# Reference_Schematic_2021-02-27.net
KiCad netlist of a schematic drawn in Altium Designer
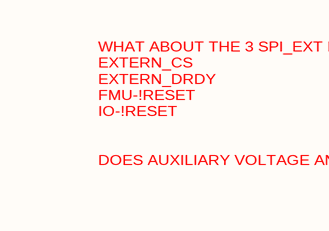
[diagram p0: Reference Schematic_2021-02-27.schdoc, top left]
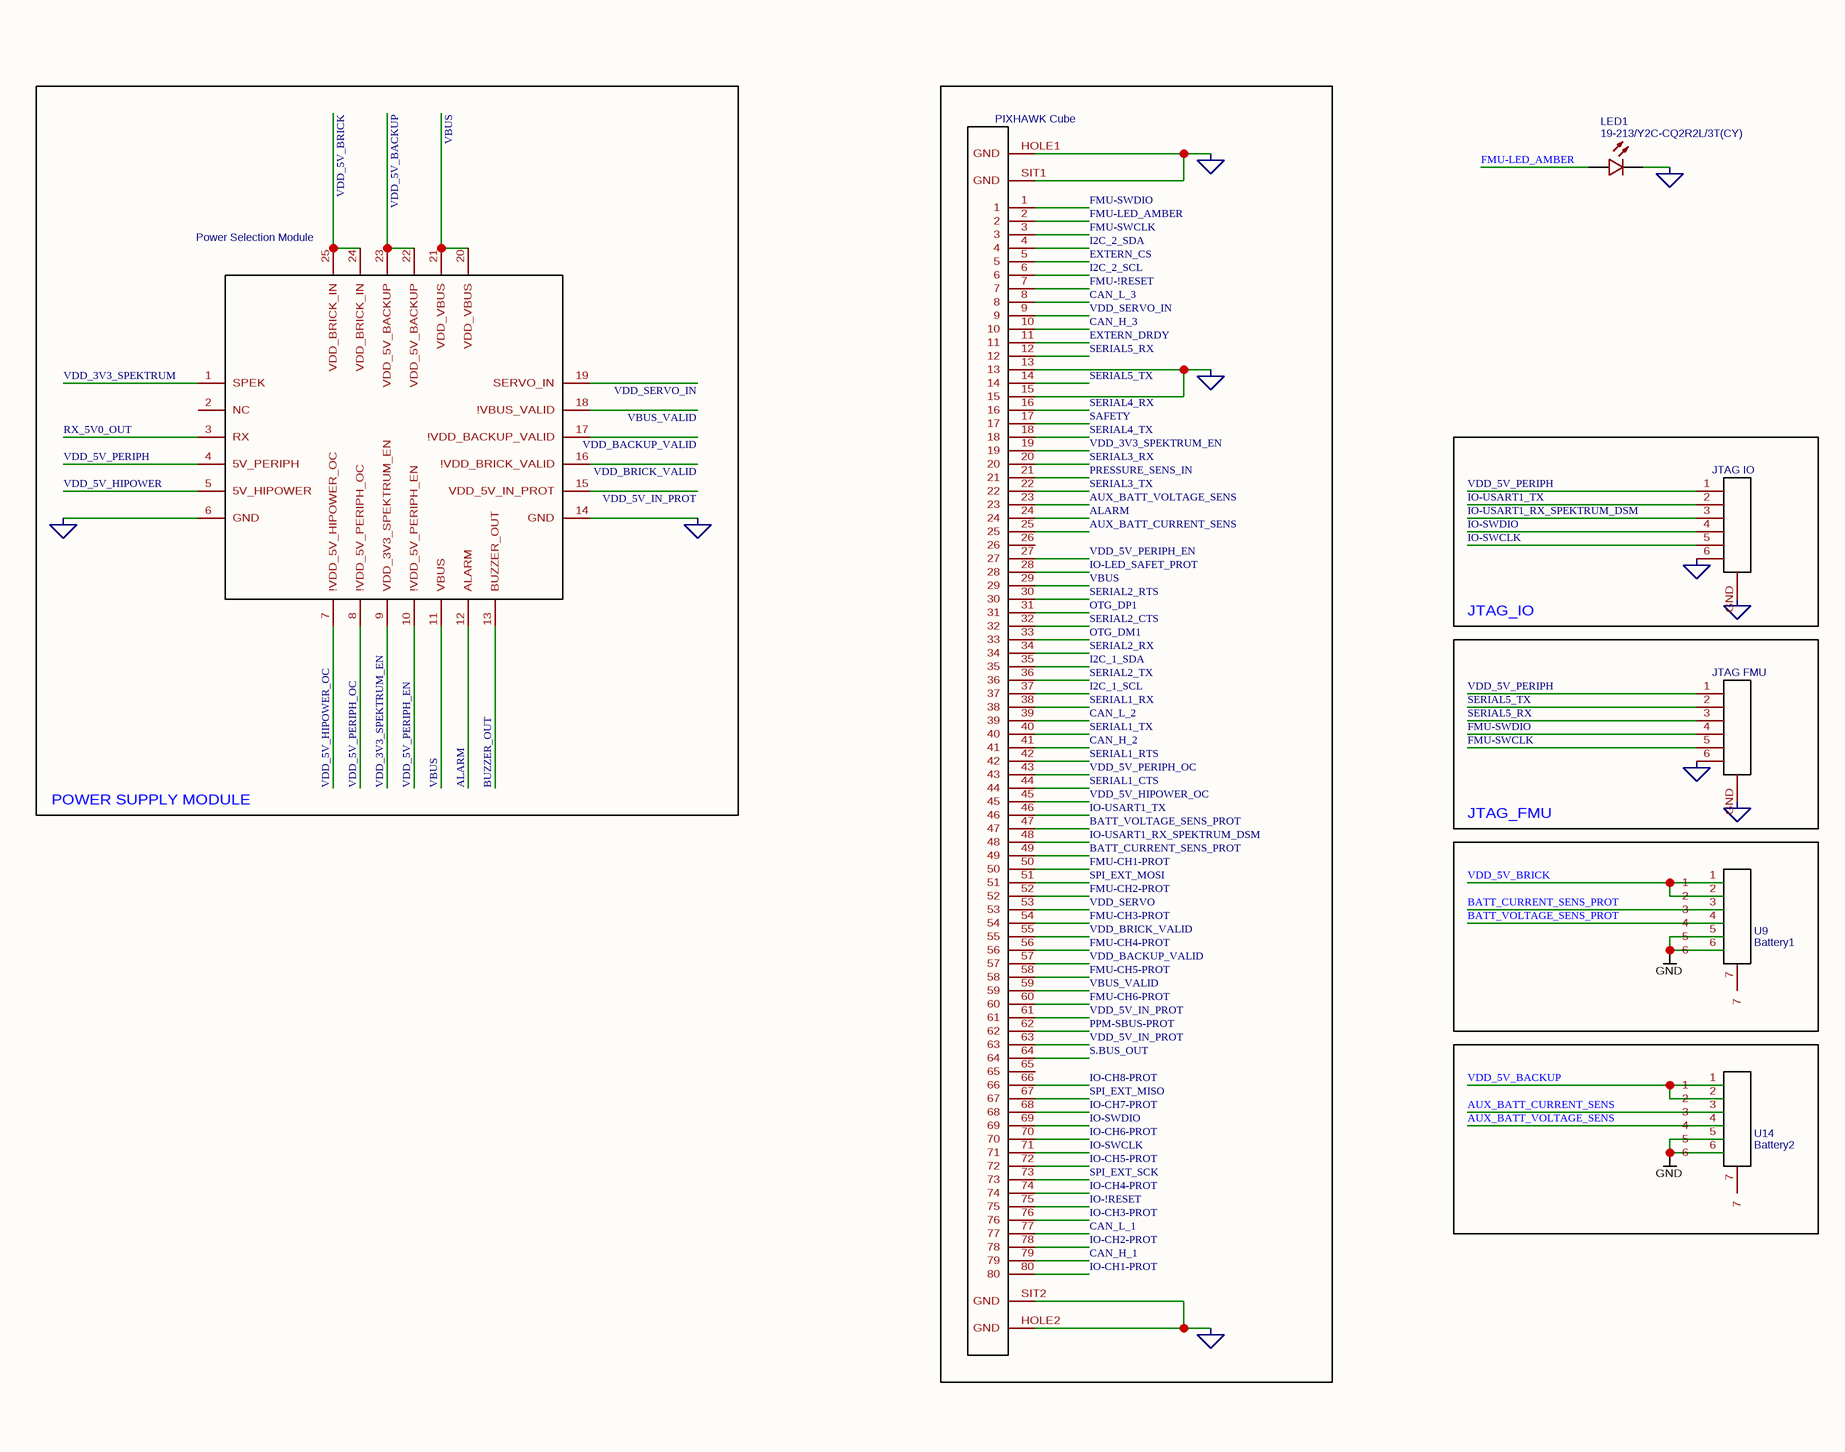
[diagram p1: Reference Schematic_2021-02-27.schdoc, bottom left]
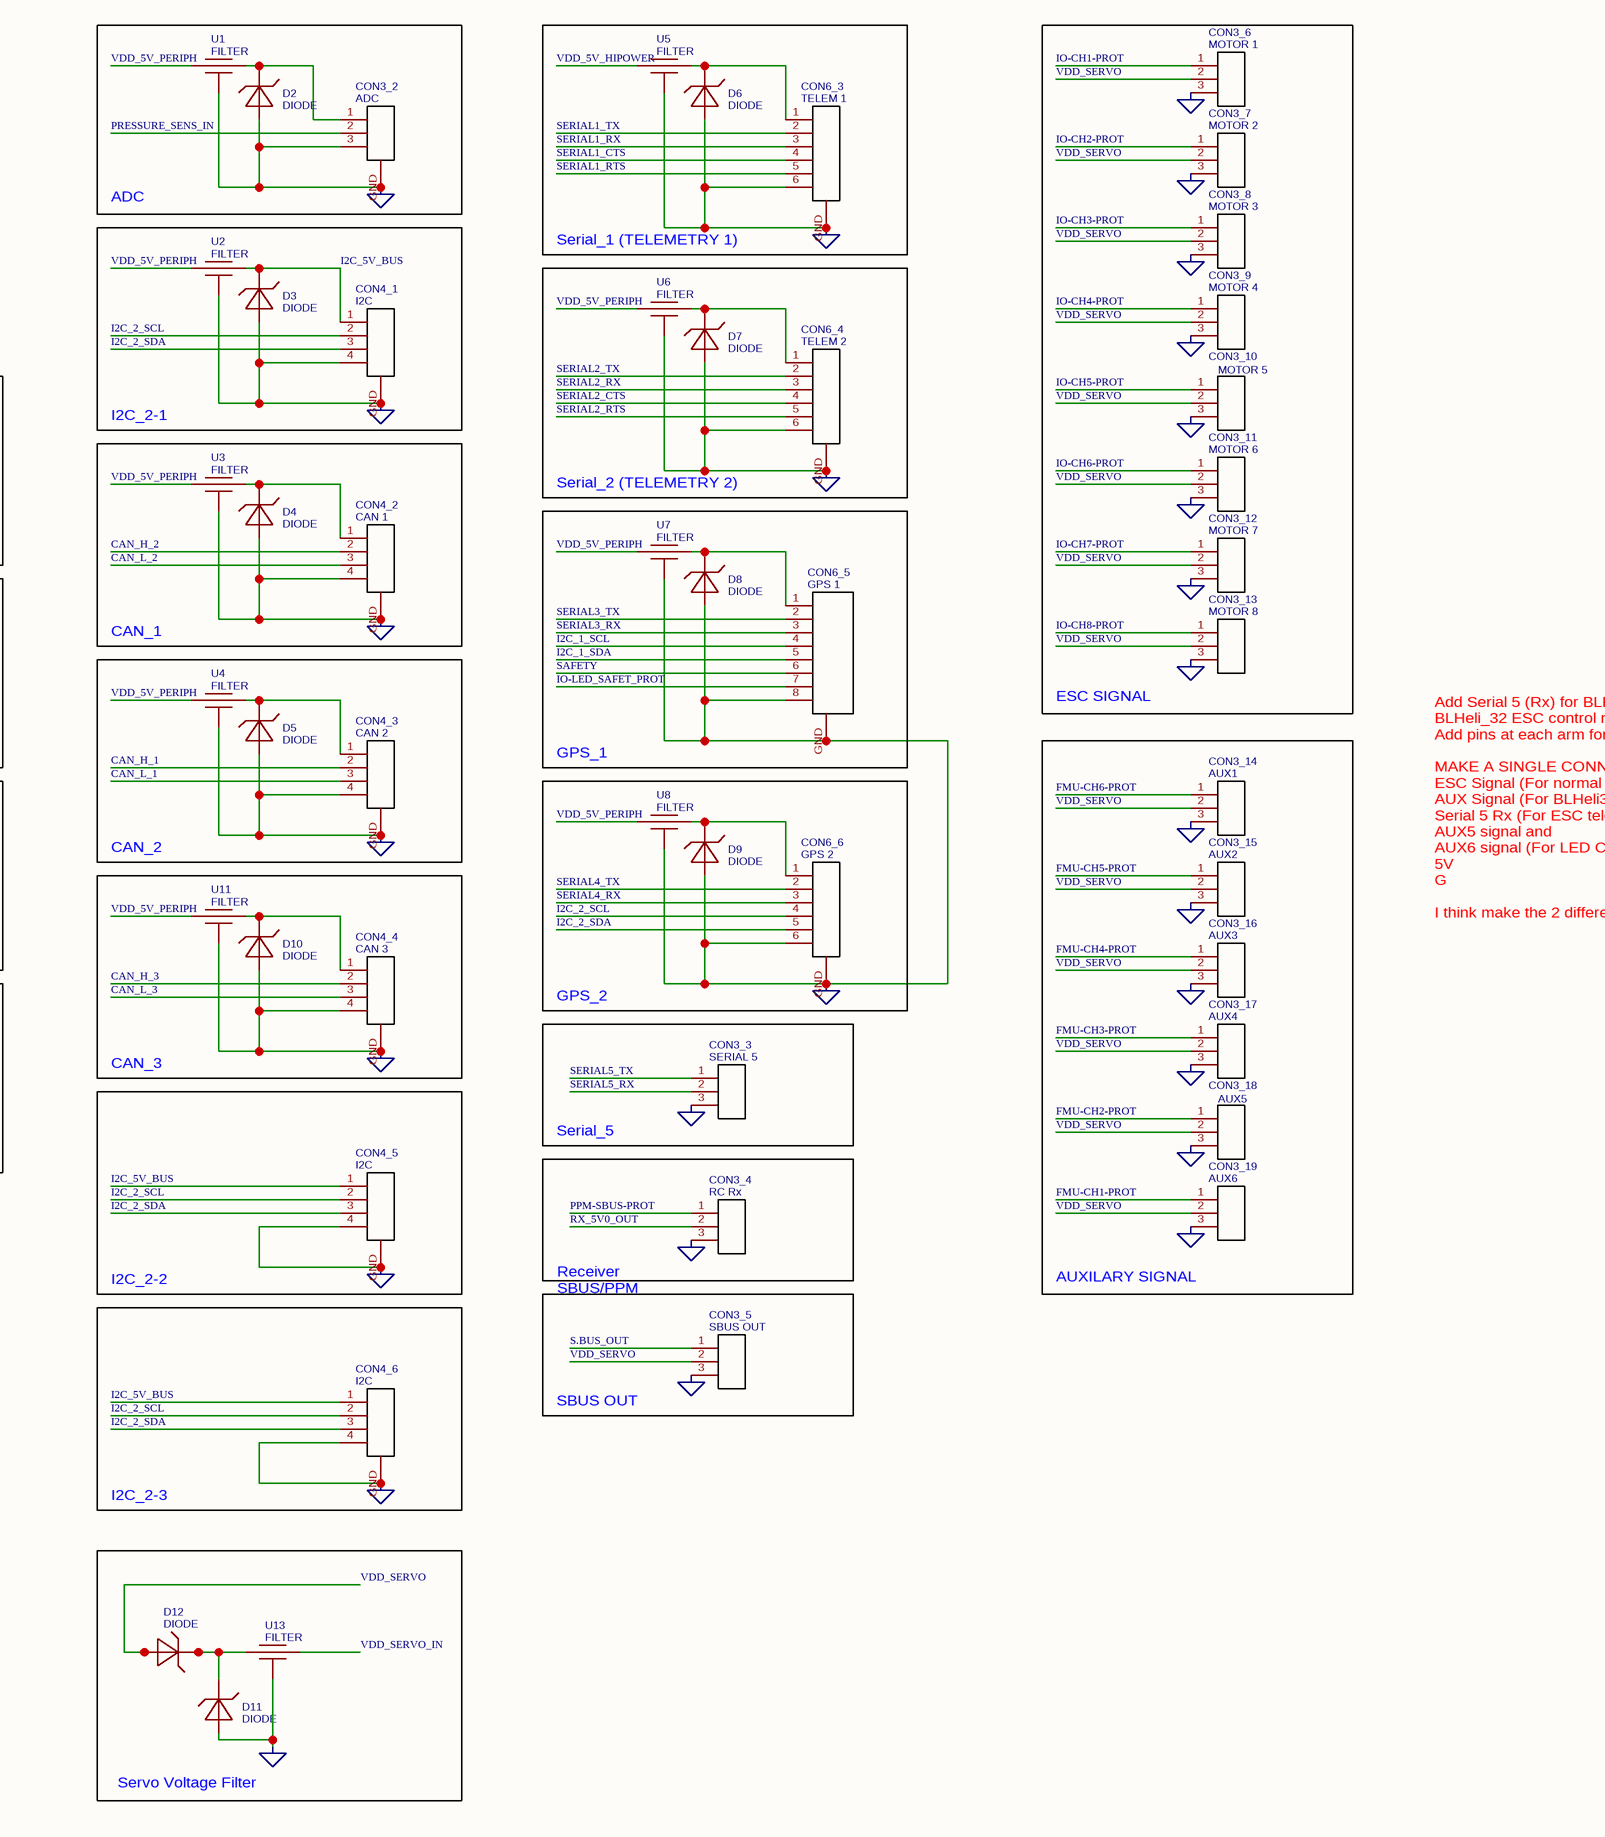
[diagram p2: Reference Schematic_2021-02-27.schdoc, bottom right]

(export (version "E")
  (design (tool "Eeschema 10.0.6"))
  (components
    (comp (ref "CON3_2")
      (value "ADC")
      (description "CONN HEADER GH TOP 3POS 1.25MM")
      (fields
        (field (name "BOM_MANUFACTURER PART") "BM03B-GHS-TBT(LF)(SN)(N)")
        (field (name "BOM_SUPPLIER PART") "455-1579-2-ND")
      )
      (libsource (lib "altium-import") (part "root_0_ADC_"))
    )
    (comp (ref "CON3_3")
      (value "SERIAL 5")
      (fields
        (field (name "BOM_MANUFACTURER PART") "894-70-012-10-001101")
        (field (name "BOM_SUPPLIER PART") "894-70-012-10-001101-ND")
      )
      (libsource (lib "altium-import") (part "root_0_SERIAL 5_"))
    )
    (comp (ref "CON3_4")
      (value "RC Rx")
      (fields
        (field (name "BOM_MANUFACTURER PART") "894-70-012-10-001101")
        (field (name "BOM_SUPPLIER PART") "894-70-012-10-001101-ND")
      )
      (libsource (lib "altium-import") (part "root_0_RC Rx_"))
    )
    (comp (ref "CON3_5")
      (value "SBUS OUT")
      (fields
        (field (name "BOM_MANUFACTURER PART") "894-70-012-10-001101")
        (field (name "BOM_SUPPLIER PART") "894-70-012-10-001101-ND")
      )
      (libsource (lib "altium-import") (part "root_0_SBUS OUT_"))
    )
    (comp (ref "CON3_6")
      (value "MOTOR 1")
      (fields
        (field (name "BOM_MANUFACTURER PART") "894-70-012-10-001101")
        (field (name "BOM_SUPPLIER PART") "894-70-012-10-001101-ND")
      )
      (libsource (lib "altium-import") (part "root_0_MOTOR 1_"))
    )
    (comp (ref "CON3_7")
      (value "MOTOR 2")
      (fields
        (field (name "BOM_MANUFACTURER PART") "894-70-012-10-001101")
        (field (name "BOM_SUPPLIER PART") "894-70-012-10-001101-ND")
      )
      (libsource (lib "altium-import") (part "root_0_MOTOR 2_"))
    )
    (comp (ref "CON3_8")
      (value "MOTOR 3")
      (fields
        (field (name "BOM_MANUFACTURER PART") "894-70-012-10-001101")
        (field (name "BOM_SUPPLIER PART") "894-70-012-10-001101-ND")
      )
      (libsource (lib "altium-import") (part "root_0_MOTOR 3_"))
    )
    (comp (ref "CON3_9")
      (value "MOTOR 4")
      (fields
        (field (name "BOM_MANUFACTURER PART") "894-70-012-10-001101")
        (field (name "BOM_SUPPLIER PART") "894-70-012-10-001101-ND")
      )
      (libsource (lib "altium-import") (part "root_0_MOTOR 4_"))
    )
    (comp (ref "CON3_10")
      (value "MOTOR 5")
      (fields
        (field (name "BOM_MANUFACTURER PART") "894-70-012-10-001101")
        (field (name "BOM_SUPPLIER PART") "894-70-012-10-001101-ND")
      )
      (libsource (lib "altium-import") (part "root_0_MOTOR 5_"))
    )
    (comp (ref "CON3_11")
      (value "MOTOR 6")
      (fields
        (field (name "BOM_MANUFACTURER PART") "894-70-012-10-001101")
        (field (name "BOM_SUPPLIER PART") "894-70-012-10-001101-ND")
      )
      (libsource (lib "altium-import") (part "root_0_MOTOR 6_"))
    )
    (comp (ref "CON3_12")
      (value "MOTOR 7")
      (fields
        (field (name "BOM_MANUFACTURER PART") "894-70-012-10-001101")
        (field (name "BOM_SUPPLIER PART") "894-70-012-10-001101-ND")
      )
      (libsource (lib "altium-import") (part "root_0_MOTOR 7_"))
    )
    (comp (ref "CON3_13")
      (value "MOTOR 8")
      (fields
        (field (name "BOM_MANUFACTURER PART") "894-70-012-10-001101")
        (field (name "BOM_SUPPLIER PART") "894-70-012-10-001101-ND")
      )
      (libsource (lib "altium-import") (part "root_0_MOTOR 8_"))
    )
    (comp (ref "CON3_14")
      (value "AUX1")
      (fields
        (field (name "BOM_MANUFACTURER PART") "894-70-012-10-001101")
        (field (name "BOM_SUPPLIER PART") "894-70-012-10-001101-ND")
      )
      (libsource (lib "altium-import") (part "root_0_AUX1_"))
    )
    (comp (ref "CON3_15")
      (value "AUX2")
      (fields
        (field (name "BOM_MANUFACTURER PART") "894-70-012-10-001101")
        (field (name "BOM_SUPPLIER PART") "894-70-012-10-001101-ND")
      )
      (libsource (lib "altium-import") (part "root_0_AUX2_"))
    )
    (comp (ref "CON3_16")
      (value "AUX3")
      (fields
        (field (name "BOM_MANUFACTURER PART") "894-70-012-10-001101")
        (field (name "BOM_SUPPLIER PART") "894-70-012-10-001101-ND")
      )
      (libsource (lib "altium-import") (part "root_0_AUX3_"))
    )
    (comp (ref "CON3_17")
      (value "AUX4")
      (fields
        (field (name "BOM_MANUFACTURER PART") "894-70-012-10-001101")
        (field (name "BOM_SUPPLIER PART") "894-70-012-10-001101-ND")
      )
      (libsource (lib "altium-import") (part "root_0_AUX4_"))
    )
    (comp (ref "CON3_18")
      (value "AUX5")
      (fields
        (field (name "BOM_MANUFACTURER PART") "894-70-012-10-001101")
        (field (name "BOM_SUPPLIER PART") "894-70-012-10-001101-ND")
      )
      (libsource (lib "altium-import") (part "root_0_AUX5_"))
    )
    (comp (ref "CON3_19")
      (value "AUX6")
      (fields
        (field (name "BOM_MANUFACTURER PART") "894-70-012-10-001101")
        (field (name "BOM_SUPPLIER PART") "894-70-012-10-001101-ND")
      )
      (libsource (lib "altium-import") (part "root_0_AUX6_"))
    )
    (comp (ref "CON4_1")
      (value "I2C")
      (description "CONN HEADER GH TOP 4POS 1.25MM")
      (fields
        (field (name "BOM_MANUFACTURER PART") "BM04B-GHS-TBT(LF)(SN)(N)")
        (field (name "BOM_SUPPLIER PART") "455-1580-2-ND")
      )
      (libsource (lib "altium-import") (part "root_0_I2C_"))
    )
    (comp (ref "CON4_2")
      (value "CAN 1")
      (description "CONN HEADER GH TOP 4POS 1.25MM")
      (fields
        (field (name "BOM_MANUFACTURER PART") "BM04B-GHS-TBT(LF)(SN)(N)")
        (field (name "BOM_SUPPLIER PART") "455-1580-2-ND")
      )
      (libsource (lib "altium-import") (part "root_0_CAN 1_"))
    )
    (comp (ref "CON4_3")
      (value "CAN 2")
      (description "CONN HEADER GH TOP 4POS 1.25MM")
      (fields
        (field (name "BOM_MANUFACTURER PART") "BM04B-GHS-TBT(LF)(SN)(N)")
        (field (name "BOM_SUPPLIER PART") "455-1580-2-ND")
      )
      (libsource (lib "altium-import") (part "root_0_CAN 2_"))
    )
    (comp (ref "CON4_4")
      (value "CAN 3")
      (description "CONN HEADER GH TOP 4POS 1.25MM")
      (fields
        (field (name "BOM_MANUFACTURER PART") "BM04B-GHS-TBT(LF)(SN)(N)")
        (field (name "BOM_SUPPLIER PART") "455-1580-2-ND")
      )
      (libsource (lib "altium-import") (part "root_0_CAN 3_"))
    )
    (comp (ref "CON4_5")
      (value "I2C")
      (description "CONN HEADER GH TOP 4POS 1.25MM")
      (fields
        (field (name "BOM_MANUFACTURER PART") "BM04B-GHS-TBT(LF)(SN)(N)")
        (field (name "BOM_SUPPLIER PART") "455-1580-2-ND")
      )
      (libsource (lib "altium-import") (part "root_0_I2C_"))
    )
    (comp (ref "CON4_6")
      (value "I2C")
      (description "CONN HEADER GH TOP 4POS 1.25MM")
      (fields
        (field (name "BOM_MANUFACTURER PART") "BM04B-GHS-TBT(LF)(SN)(N)")
        (field (name "BOM_SUPPLIER PART") "455-1580-2-ND")
      )
      (libsource (lib "altium-import") (part "root_0_I2C_"))
    )
    (comp (ref "CON6_1")
      (value "JTAG IO")
      (description "CONN HEADER SUR 6POS .8MM IDC")
      (fields
        (field (name "BOM_MANUFACTURER PART") "SM06B-SURS-TF(LF)(SN)")
        (field (name "BOM_SUPPLIER PART") "SM06B-SURS-TF(LF)(SN)-ND")
      )
      (libsource (lib "altium-import") (part "root_0_JTAG IO_"))
    )
    (comp (ref "CON6_2")
      (value "JTAG FMU")
      (description "CONN HEADER SUR 6POS .8MM IDC")
      (fields
        (field (name "BOM_MANUFACTURER PART") "SM06B-SURS-TF(LF)(SN)")
        (field (name "BOM_SUPPLIER PART") "SM06B-SURS-TF(LF)(SN)-ND")
      )
      (libsource (lib "altium-import") (part "root_0_JTAG FMU_"))
    )
    (comp (ref "CON6_3")
      (value "TELEM 1")
      (description "CONN HEADER GH TOP 6POS 1.25MM")
      (fields
        (field (name "BOM_MANUFACTURER PART") "BM06B-GHS-TBT(LF)(SN)(N)")
        (field (name "BOM_SUPPLIER PART") "455-1582-2-ND")
      )
      (libsource (lib "altium-import") (part "root_0_TELEM 1_"))
    )
    (comp (ref "CON6_4")
      (value "TELEM 2")
      (description "CONN HEADER GH TOP 6POS 1.25MM")
      (fields
        (field (name "BOM_MANUFACTURER PART") "BM06B-GHS-TBT(LF)(SN)(N)")
        (field (name "BOM_SUPPLIER PART") "455-1582-2-ND")
      )
      (libsource (lib "altium-import") (part "root_0_TELEM 2_"))
    )
    (comp (ref "CON6_5")
      (value "GPS 1")
      (description "CONN HEADER GH TOP 8POS 1.25MM")
      (fields
        (field (name "BOM_MANUFACTURER PART") "BM08B-GHS-TBT(LF)(SN)(N)")
        (field (name "BOM_SUPPLIER PART") "455-1584-2-ND")
      )
      (libsource (lib "altium-import") (part "root_0_GPS 1_"))
    )
    (comp (ref "CON6_6")
      (value "GPS 2")
      (description "CONN HEADER GH TOP 6POS 1.25MM")
      (fields
        (field (name "BOM_MANUFACTURER PART") "BM06B-GHS-TBT(LF)(SN)(N)")
        (field (name "BOM_SUPPLIER PART") "455-1582-2-ND")
      )
      (libsource (lib "altium-import") (part "root_0_GPS 2_"))
    )
    (comp (ref "D2")
      (value "DIODE")
      (fields
        (field (name "BOM_MANUFACTURER PART") "PESD0402-140")
        (field (name "BOM_SUPPLIER PART") "650-PESD0402-140")
      )
      (libsource (lib "altium-import") (part "root_3_DIODE_"))
    )
    (comp (ref "D3")
      (value "DIODE")
      (fields
        (field (name "BOM_MANUFACTURER PART") "PESD0402-140")
        (field (name "BOM_SUPPLIER PART") "650-PESD0402-140")
      )
      (libsource (lib "altium-import") (part "root_3_DIODE_"))
    )
    (comp (ref "D4")
      (value "DIODE")
      (fields
        (field (name "BOM_MANUFACTURER PART") "PESD0402-140")
        (field (name "BOM_SUPPLIER PART") "650-PESD0402-140")
      )
      (libsource (lib "altium-import") (part "root_3_DIODE_"))
    )
    (comp (ref "D5")
      (value "DIODE")
      (fields
        (field (name "BOM_MANUFACTURER PART") "PESD0402-140")
        (field (name "BOM_SUPPLIER PART") "650-PESD0402-140")
      )
      (libsource (lib "altium-import") (part "root_3_DIODE_"))
    )
    (comp (ref "D6")
      (value "DIODE")
      (fields
        (field (name "BOM_MANUFACTURER PART") "PESD0402-140")
        (field (name "BOM_SUPPLIER PART") "650-PESD0402-140")
      )
      (libsource (lib "altium-import") (part "root_3_DIODE_"))
    )
    (comp (ref "D7")
      (value "DIODE")
      (fields
        (field (name "BOM_MANUFACTURER PART") "PESD0402-140")
        (field (name "BOM_SUPPLIER PART") "650-PESD0402-140")
      )
      (libsource (lib "altium-import") (part "root_3_DIODE_"))
    )
    (comp (ref "D8")
      (value "DIODE")
      (fields
        (field (name "BOM_MANUFACTURER PART") "PESD0402-140")
        (field (name "BOM_SUPPLIER PART") "650-PESD0402-140")
      )
      (libsource (lib "altium-import") (part "root_3_DIODE_"))
    )
    (comp (ref "D9")
      (value "DIODE")
      (fields
        (field (name "BOM_MANUFACTURER PART") "PESD0402-140")
        (field (name "BOM_SUPPLIER PART") "650-PESD0402-140")
      )
      (libsource (lib "altium-import") (part "root_3_DIODE_"))
    )
    (comp (ref "D10")
      (value "DIODE")
      (fields
        (field (name "BOM_MANUFACTURER PART") "PESD0402-140")
        (field (name "BOM_SUPPLIER PART") "650-PESD0402-140")
      )
      (libsource (lib "altium-import") (part "root_3_DIODE_"))
    )
    (comp (ref "D11")
      (value "DIODE")
      (fields
        (field (name "BOM_MANUFACTURER PART") "PESD0402-140")
        (field (name "BOM_SUPPLIER PART") "650-PESD0402-140")
      )
      (libsource (lib "altium-import") (part "root_3_DIODE_"))
    )
    (comp (ref "D12")
      (value "DIODE")
      (fields
        (field (name "BOM_MANUFACTURER PART") "MSS1P4-M3/89A")
        (field (name "BOM_SUPPLIER PART") "05W6894")
      )
      (libsource (lib "altium-import") (part "root_2_DIODE_"))
    )
    (comp (ref "DF17(1.0H)-80DP-0.5V(57)")
      (value "PIXHAWK Cube")
      (fields
        (field (name "BOM_MANUFACTURER PART") "DF17(1.0H)-80DP-0.5V(57)")
        (field (name "BOM_SUPPLIER PART") "798-DF1710H80DP05V57")
      )
      (libsource (lib "altium-import") (part "root_0_PIXHAWK Cube_"))
    )
    (comp (ref "LED1")
      (value "19-213/Y2C-CQ2R2L/3T(CY)")
      (fields (field (name "BOM_SUPPLIER PART") "C72038"))
      (libsource (lib "altium-import") (part "root_0_19-213/Y2C-CQ2R2L/3T(CY)_"))
    )
    (comp (ref "PSM")
      (value "Power Selection Module")
      (fields (field (name "BOM_SUPPLIER PART") "PSM_C"))
      (libsource (lib "altium-import") (part "root_0_Power Selection Module_"))
    )
    (comp (ref "U1")
      (value "FILTER")
      (fields
        (field (name "BOM_MANUFACTURER PART") "NFM18PC104R1C3D")
        (field (name "BOM_SUPPLIER PART") "490-6969-2-ND")
      )
      (libsource (lib "altium-import") (part "root_0_FILTER_"))
    )
    (comp (ref "U2")
      (value "FILTER")
      (fields
        (field (name "BOM_MANUFACTURER PART") "NFM18PC104R1C3D")
        (field (name "BOM_SUPPLIER PART") "490-6969-2-ND")
      )
      (libsource (lib "altium-import") (part "root_0_FILTER_"))
    )
    (comp (ref "U3")
      (value "FILTER")
      (fields
        (field (name "BOM_MANUFACTURER PART") "NFM18PC104R1C3D")
        (field (name "BOM_SUPPLIER PART") "490-6969-2-ND")
      )
      (libsource (lib "altium-import") (part "root_0_FILTER_"))
    )
    (comp (ref "U4")
      (value "FILTER")
      (fields
        (field (name "BOM_MANUFACTURER PART") "NFM18PC104R1C3D")
        (field (name "BOM_SUPPLIER PART") "490-6969-2-ND")
      )
      (libsource (lib "altium-import") (part "root_0_FILTER_"))
    )
    (comp (ref "U5")
      (value "FILTER")
      (fields
        (field (name "BOM_MANUFACTURER PART") "NFM18PC104R1C3D")
        (field (name "BOM_SUPPLIER PART") "490-6969-2-ND")
      )
      (libsource (lib "altium-import") (part "root_0_FILTER_"))
    )
    (comp (ref "U6")
      (value "FILTER")
      (fields
        (field (name "BOM_MANUFACTURER PART") "NFM18PC104R1C3D")
        (field (name "BOM_SUPPLIER PART") "490-6969-2-ND")
      )
      (libsource (lib "altium-import") (part "root_0_FILTER_"))
    )
    (comp (ref "U7")
      (value "FILTER")
      (fields
        (field (name "BOM_MANUFACTURER PART") "NFM18PC104R1C3D")
        (field (name "BOM_SUPPLIER PART") "490-6969-2-ND")
      )
      (libsource (lib "altium-import") (part "root_0_FILTER_"))
    )
    (comp (ref "U8")
      (value "FILTER")
      (fields
        (field (name "BOM_MANUFACTURER PART") "NFM18PC104R1C3D")
        (field (name "BOM_SUPPLIER PART") "490-6969-2-ND")
      )
      (libsource (lib "altium-import") (part "root_0_FILTER_"))
    )
    (comp (ref "U9")
      (value "Battery1")
      (fields (field (name "BOM_MANUFACTURER PART") "502443-0670"))
      (libsource (lib "altium-import") (part "root_0_Battery1_"))
    )
    (comp (ref "U11")
      (value "FILTER")
      (fields
        (field (name "BOM_MANUFACTURER PART") "NFM18PC104R1C3D")
        (field (name "BOM_SUPPLIER PART") "490-6969-2-ND")
      )
      (libsource (lib "altium-import") (part "root_0_FILTER_"))
    )
    (comp (ref "U13")
      (value "FILTER")
      (fields
        (field (name "BOM_MANUFACTURER PART") "NFM18PC104R1C3D")
        (field (name "BOM_SUPPLIER PART") "490-6969-2-ND")
      )
      (libsource (lib "altium-import") (part "root_0_FILTER_"))
    )
    (comp (ref "U14")
      (value "Battery2")
      (fields (field (name "BOM_MANUFACTURER PART") "502443-0670"))
      (libsource (lib "altium-import") (part "root_0_Battery2_"))
    )
  )
  (nets
    (net (code "1") (name "/ALARM") (class "Default")
      (node (ref "DF17(1.0H)-80DP-0.5V(57)") (pin "24") (pinfunction "24_24") (pintype "passive"))
      (node (ref "PSM") (pin "12") (pinfunction "ALARM_12") (pintype "passive"))
    )
    (net (code "2") (name "/AUX_BATT_CURRENT_SENS") (class "Default")
      (node (ref "DF17(1.0H)-80DP-0.5V(57)") (pin "25") (pinfunction "25_25") (pintype "passive"))
      (node (ref "U14") (pin "3") (pinfunction "3_3") (pintype "passive"))
    )
    (net (code "3") (name "/AUX_BATT_VOLTAGE_SENS") (class "Default")
      (node (ref "DF17(1.0H)-80DP-0.5V(57)") (pin "23") (pinfunction "23_23") (pintype "passive"))
      (node (ref "U14") (pin "4") (pinfunction "4_4") (pintype "passive"))
    )
    (net (code "4") (name "/BATT_CURRENT_SENS_PROT") (class "Default")
      (node (ref "DF17(1.0H)-80DP-0.5V(57)") (pin "49") (pinfunction "49_49") (pintype "passive"))
      (node (ref "U9") (pin "3") (pinfunction "3_3") (pintype "passive"))
    )
    (net (code "5") (name "/BATT_VOLTAGE_SENS_PROT") (class "Default")
      (node (ref "DF17(1.0H)-80DP-0.5V(57)") (pin "47") (pinfunction "47_47") (pintype "passive"))
      (node (ref "U9") (pin "4") (pinfunction "4_4") (pintype "passive"))
    )
    (net (code "6") (name "/BUZZER_OUT") (class "Default")
      (node (ref "PSM") (pin "13") (pinfunction "BUZZER_OUT_13") (pintype "passive"))
    )
    (net (code "7") (name "/CAN_H_1") (class "Default")
      (node (ref "CON4_3") (pin "2") (pinfunction "2_2") (pintype "passive"))
      (node (ref "DF17(1.0H)-80DP-0.5V(57)") (pin "79") (pinfunction "79_79") (pintype "passive"))
    )
    (net (code "8") (name "/CAN_H_2") (class "Default")
      (node (ref "CON4_2") (pin "2") (pinfunction "2_2") (pintype "passive"))
      (node (ref "DF17(1.0H)-80DP-0.5V(57)") (pin "41") (pinfunction "41_41") (pintype "passive"))
    )
    (net (code "9") (name "/CAN_H_3") (class "Default")
      (node (ref "CON4_4") (pin "2") (pinfunction "2_2") (pintype "passive"))
      (node (ref "DF17(1.0H)-80DP-0.5V(57)") (pin "10") (pinfunction "10_10") (pintype "passive"))
    )
    (net (code "10") (name "/CAN_L_1") (class "Default")
      (node (ref "CON4_3") (pin "3") (pinfunction "3_3") (pintype "passive"))
      (node (ref "DF17(1.0H)-80DP-0.5V(57)") (pin "77") (pinfunction "77_77") (pintype "passive"))
    )
    (net (code "11") (name "/CAN_L_2") (class "Default")
      (node (ref "CON4_2") (pin "3") (pinfunction "3_3") (pintype "passive"))
      (node (ref "DF17(1.0H)-80DP-0.5V(57)") (pin "39") (pinfunction "39_39") (pintype "passive"))
    )
    (net (code "12") (name "/CAN_L_3") (class "Default")
      (node (ref "CON4_4") (pin "3") (pinfunction "3_3") (pintype "passive"))
      (node (ref "DF17(1.0H)-80DP-0.5V(57)") (pin "8") (pinfunction "8_8") (pintype "passive"))
    )
    (net (code "13") (name "/EXTERN_CS") (class "Default")
      (node (ref "DF17(1.0H)-80DP-0.5V(57)") (pin "5") (pinfunction "5_5") (pintype "passive"))
    )
    (net (code "14") (name "/EXTERN_DRDY") (class "Default")
      (node (ref "DF17(1.0H)-80DP-0.5V(57)") (pin "11") (pinfunction "11_11") (pintype "passive"))
    )
    (net (code "15") (name "/FMU-!RESET") (class "Default")
      (node (ref "DF17(1.0H)-80DP-0.5V(57)") (pin "7") (pinfunction "7_7") (pintype "passive"))
    )
    (net (code "16") (name "/FMU-CH1-PROT") (class "Default")
      (node (ref "CON3_19") (pin "1") (pinfunction "1_1") (pintype "passive"))
      (node (ref "DF17(1.0H)-80DP-0.5V(57)") (pin "50") (pinfunction "50_50") (pintype "passive"))
    )
    (net (code "17") (name "/FMU-CH2-PROT") (class "Default")
      (node (ref "CON3_18") (pin "1") (pinfunction "1_1") (pintype "passive"))
      (node (ref "DF17(1.0H)-80DP-0.5V(57)") (pin "52") (pinfunction "52_52") (pintype "passive"))
    )
    (net (code "18") (name "/FMU-CH3-PROT") (class "Default")
      (node (ref "CON3_17") (pin "1") (pinfunction "1_1") (pintype "passive"))
      (node (ref "DF17(1.0H)-80DP-0.5V(57)") (pin "54") (pinfunction "54_54") (pintype "passive"))
    )
    (net (code "19") (name "/FMU-CH4-PROT") (class "Default")
      (node (ref "CON3_16") (pin "1") (pinfunction "1_1") (pintype "passive"))
      (node (ref "DF17(1.0H)-80DP-0.5V(57)") (pin "56") (pinfunction "56_56") (pintype "passive"))
    )
    (net (code "20") (name "/FMU-CH5-PROT") (class "Default")
      (node (ref "CON3_15") (pin "1") (pinfunction "1_1") (pintype "passive"))
      (node (ref "DF17(1.0H)-80DP-0.5V(57)") (pin "58") (pinfunction "58_58") (pintype "passive"))
    )
    (net (code "21") (name "/FMU-CH6-PROT") (class "Default")
      (node (ref "CON3_14") (pin "1") (pinfunction "1_1") (pintype "passive"))
      (node (ref "DF17(1.0H)-80DP-0.5V(57)") (pin "60") (pinfunction "60_60") (pintype "passive"))
    )
    (net (code "22") (name "/FMU-LED_AMBER") (class "Default")
      (node (ref "DF17(1.0H)-80DP-0.5V(57)") (pin "2") (pinfunction "2_2") (pintype "passive"))
      (node (ref "LED1") (pin "1") (pinfunction "A_1") (pintype "passive"))
    )
    (net (code "23") (name "/FMU-SWCLK") (class "Default")
      (node (ref "CON6_2") (pin "5") (pinfunction "5_5") (pintype "passive"))
      (node (ref "DF17(1.0H)-80DP-0.5V(57)") (pin "3") (pinfunction "3_3") (pintype "passive"))
    )
    (net (code "24") (name "/FMU-SWDIO") (class "Default")
      (node (ref "CON6_2") (pin "4") (pinfunction "4_4") (pintype "passive"))
      (node (ref "DF17(1.0H)-80DP-0.5V(57)") (pin "1") (pinfunction "1_1") (pintype "passive"))
    )
    (net (code "25") (name "/I2C_1_SCL") (class "Default")
      (node (ref "CON6_5") (pin "4") (pinfunction "4_4") (pintype "passive"))
      (node (ref "DF17(1.0H)-80DP-0.5V(57)") (pin "37") (pinfunction "37_37") (pintype "passive"))
    )
    (net (code "26") (name "/I2C_1_SDA") (class "Default")
      (node (ref "CON6_5") (pin "5") (pinfunction "5_5") (pintype "passive"))
      (node (ref "DF17(1.0H)-80DP-0.5V(57)") (pin "35") (pinfunction "35_35") (pintype "passive"))
    )
    (net (code "27") (name "/I2C_2_SCL") (class "Default")
      (node (ref "CON4_1") (pin "2") (pinfunction "2_2") (pintype "passive"))
      (node (ref "CON4_5") (pin "2") (pinfunction "2_2") (pintype "passive"))
      (node (ref "CON4_6") (pin "2") (pinfunction "2_2") (pintype "passive"))
      (node (ref "CON6_6") (pin "4") (pinfunction "4_4") (pintype "passive"))
      (node (ref "DF17(1.0H)-80DP-0.5V(57)") (pin "6") (pinfunction "6_6") (pintype "passive"))
    )
    (net (code "28") (name "/I2C_2_SDA") (class "Default")
      (node (ref "CON4_1") (pin "3") (pinfunction "3_3") (pintype "passive"))
      (node (ref "CON4_5") (pin "3") (pinfunction "3_3") (pintype "passive"))
      (node (ref "CON4_6") (pin "3") (pinfunction "3_3") (pintype "passive"))
      (node (ref "CON6_6") (pin "5") (pinfunction "5_5") (pintype "passive"))
      (node (ref "DF17(1.0H)-80DP-0.5V(57)") (pin "4") (pinfunction "4_4") (pintype "passive"))
    )
    (net (code "29") (name "/I2C_5V_BUS") (class "Default")
      (node (ref "CON4_1") (pin "1") (pinfunction "1_1") (pintype "passive"))
      (node (ref "CON4_5") (pin "1") (pinfunction "1_1") (pintype "passive"))
      (node (ref "CON4_6") (pin "1") (pinfunction "1_1") (pintype "passive"))
      (node (ref "D3") (pin "1") (pinfunction "1_1") (pintype "passive"))
      (node (ref "U2") (pin "2") (pinfunction "2_2") (pintype "passive"))
    )
    (net (code "30") (name "/IO-!RESET") (class "Default")
      (node (ref "DF17(1.0H)-80DP-0.5V(57)") (pin "75") (pinfunction "75_75") (pintype "passive"))
    )
    (net (code "31") (name "/IO-CH1-PROT") (class "Default")
      (node (ref "CON3_6") (pin "1") (pinfunction "1_1") (pintype "passive"))
      (node (ref "DF17(1.0H)-80DP-0.5V(57)") (pin "80") (pinfunction "80_80") (pintype "passive"))
    )
    (net (code "32") (name "/IO-CH2-PROT") (class "Default")
      (node (ref "CON3_7") (pin "1") (pinfunction "1_1") (pintype "passive"))
      (node (ref "DF17(1.0H)-80DP-0.5V(57)") (pin "78") (pinfunction "78_78") (pintype "passive"))
    )
    (net (code "33") (name "/IO-CH3-PROT") (class "Default")
      (node (ref "CON3_8") (pin "1") (pinfunction "1_1") (pintype "passive"))
      (node (ref "DF17(1.0H)-80DP-0.5V(57)") (pin "76") (pinfunction "76_76") (pintype "passive"))
    )
    (net (code "34") (name "/IO-CH4-PROT") (class "Default")
      (node (ref "CON3_9") (pin "1") (pinfunction "1_1") (pintype "passive"))
      (node (ref "DF17(1.0H)-80DP-0.5V(57)") (pin "74") (pinfunction "74_74") (pintype "passive"))
    )
    (net (code "35") (name "/IO-CH5-PROT") (class "Default")
      (node (ref "CON3_10") (pin "1") (pinfunction "1_1") (pintype "passive"))
      (node (ref "DF17(1.0H)-80DP-0.5V(57)") (pin "72") (pinfunction "72_72") (pintype "passive"))
    )
    (net (code "36") (name "/IO-CH6-PROT") (class "Default")
      (node (ref "CON3_11") (pin "1") (pinfunction "1_1") (pintype "passive"))
      (node (ref "DF17(1.0H)-80DP-0.5V(57)") (pin "70") (pinfunction "70_70") (pintype "passive"))
    )
    (net (code "37") (name "/IO-CH7-PROT") (class "Default")
      (node (ref "CON3_12") (pin "1") (pinfunction "1_1") (pintype "passive"))
      (node (ref "DF17(1.0H)-80DP-0.5V(57)") (pin "68") (pinfunction "68_68") (pintype "passive"))
    )
    (net (code "38") (name "/IO-CH8-PROT") (class "Default")
      (node (ref "CON3_13") (pin "1") (pinfunction "1_1") (pintype "passive"))
      (node (ref "DF17(1.0H)-80DP-0.5V(57)") (pin "66") (pinfunction "66_66") (pintype "passive"))
    )
    (net (code "39") (name "/IO-LED_SAFET_PROT") (class "Default")
      (node (ref "CON6_5") (pin "7") (pinfunction "7_7") (pintype "passive"))
      (node (ref "DF17(1.0H)-80DP-0.5V(57)") (pin "28") (pinfunction "28_28") (pintype "passive"))
    )
    (net (code "40") (name "/IO-SWCLK") (class "Default")
      (node (ref "CON6_1") (pin "5") (pinfunction "5_5") (pintype "passive"))
      (node (ref "DF17(1.0H)-80DP-0.5V(57)") (pin "71") (pinfunction "71_71") (pintype "passive"))
    )
    (net (code "41") (name "/IO-SWDIO") (class "Default")
      (node (ref "CON6_1") (pin "4") (pinfunction "4_4") (pintype "passive"))
      (node (ref "DF17(1.0H)-80DP-0.5V(57)") (pin "69") (pinfunction "69_69") (pintype "passive"))
    )
    (net (code "42") (name "/IO-USART1_RX_SPEKTRUM_DSM") (class "Default")
      (node (ref "CON6_1") (pin "3") (pinfunction "3_3") (pintype "passive"))
      (node (ref "DF17(1.0H)-80DP-0.5V(57)") (pin "48") (pinfunction "48_48") (pintype "passive"))
    )
    (net (code "43") (name "/IO-USART1_TX") (class "Default")
      (node (ref "CON6_1") (pin "2") (pinfunction "2_2") (pintype "passive"))
      (node (ref "DF17(1.0H)-80DP-0.5V(57)") (pin "46") (pinfunction "46_46") (pintype "passive"))
    )
    (net (code "44") (name "/OTG_DM1") (class "Default")
      (node (ref "DF17(1.0H)-80DP-0.5V(57)") (pin "33") (pinfunction "33_33") (pintype "passive"))
    )
    (net (code "45") (name "/OTG_DP1") (class "Default")
      (node (ref "DF17(1.0H)-80DP-0.5V(57)") (pin "31") (pinfunction "31_31") (pintype "passive"))
    )
    (net (code "46") (name "/PPM-SBUS-PROT") (class "Default")
      (node (ref "CON3_4") (pin "1") (pinfunction "1_1") (pintype "passive"))
      (node (ref "DF17(1.0H)-80DP-0.5V(57)") (pin "62") (pinfunction "62_62") (pintype "passive"))
    )
    (net (code "47") (name "/PRESSURE_SENS_IN") (class "Default")
      (node (ref "CON3_2") (pin "2") (pinfunction "2_2") (pintype "passive"))
      (node (ref "DF17(1.0H)-80DP-0.5V(57)") (pin "21") (pinfunction "21_21") (pintype "passive"))
    )
    (net (code "48") (name "/RX_5V0_OUT") (class "Default")
      (node (ref "CON3_4") (pin "2") (pinfunction "2_2") (pintype "passive"))
      (node (ref "PSM") (pin "3") (pinfunction "RX_3") (pintype "passive"))
    )
    (net (code "49") (name "/S.BUS_OUT") (class "Default")
      (node (ref "CON3_5") (pin "1") (pinfunction "1_1") (pintype "passive"))
      (node (ref "DF17(1.0H)-80DP-0.5V(57)") (pin "64") (pinfunction "64_64") (pintype "passive"))
    )
    (net (code "50") (name "/SAFETY") (class "Default")
      (node (ref "CON6_5") (pin "6") (pinfunction "6_6") (pintype "passive"))
      (node (ref "DF17(1.0H)-80DP-0.5V(57)") (pin "17") (pinfunction "17_17") (pintype "passive"))
    )
    (net (code "51") (name "/SERIAL1_CTS") (class "Default")
      (node (ref "CON6_3") (pin "4") (pinfunction "4_4") (pintype "passive"))
      (node (ref "DF17(1.0H)-80DP-0.5V(57)") (pin "44") (pinfunction "44_44") (pintype "passive"))
    )
    (net (code "52") (name "/SERIAL1_RTS") (class "Default")
      (node (ref "CON6_3") (pin "5") (pinfunction "5_5") (pintype "passive"))
      (node (ref "DF17(1.0H)-80DP-0.5V(57)") (pin "42") (pinfunction "42_42") (pintype "passive"))
    )
    (net (code "53") (name "/SERIAL1_RX") (class "Default")
      (node (ref "CON6_3") (pin "3") (pinfunction "3_3") (pintype "passive"))
      (node (ref "DF17(1.0H)-80DP-0.5V(57)") (pin "38") (pinfunction "38_38") (pintype "passive"))
    )
    (net (code "54") (name "/SERIAL1_TX") (class "Default")
      (node (ref "CON6_3") (pin "2") (pinfunction "2_2") (pintype "passive"))
      (node (ref "DF17(1.0H)-80DP-0.5V(57)") (pin "40") (pinfunction "40_40") (pintype "passive"))
    )
    (net (code "55") (name "/SERIAL2_CTS") (class "Default")
      (node (ref "CON6_4") (pin "4") (pinfunction "4_4") (pintype "passive"))
      (node (ref "DF17(1.0H)-80DP-0.5V(57)") (pin "32") (pinfunction "32_32") (pintype "passive"))
    )
    (net (code "56") (name "/SERIAL2_RTS") (class "Default")
      (node (ref "CON6_4") (pin "5") (pinfunction "5_5") (pintype "passive"))
      (node (ref "DF17(1.0H)-80DP-0.5V(57)") (pin "30") (pinfunction "30_30") (pintype "passive"))
    )
    (net (code "57") (name "/SERIAL2_RX") (class "Default")
      (node (ref "CON6_4") (pin "3") (pinfunction "3_3") (pintype "passive"))
      (node (ref "DF17(1.0H)-80DP-0.5V(57)") (pin "34") (pinfunction "34_34") (pintype "passive"))
    )
    (net (code "58") (name "/SERIAL2_TX") (class "Default")
      (node (ref "CON6_4") (pin "2") (pinfunction "2_2") (pintype "passive"))
      (node (ref "DF17(1.0H)-80DP-0.5V(57)") (pin "36") (pinfunction "36_36") (pintype "passive"))
    )
    (net (code "59") (name "/SERIAL3_RX") (class "Default")
      (node (ref "CON6_5") (pin "3") (pinfunction "3_3") (pintype "passive"))
      (node (ref "DF17(1.0H)-80DP-0.5V(57)") (pin "20") (pinfunction "20_20") (pintype "passive"))
    )
    (net (code "60") (name "/SERIAL3_TX") (class "Default")
      (node (ref "CON6_5") (pin "2") (pinfunction "2_2") (pintype "passive"))
      (node (ref "DF17(1.0H)-80DP-0.5V(57)") (pin "22") (pinfunction "22_22") (pintype "passive"))
    )
    (net (code "61") (name "/SERIAL4_RX") (class "Default")
      (node (ref "CON6_6") (pin "3") (pinfunction "3_3") (pintype "passive"))
      (node (ref "DF17(1.0H)-80DP-0.5V(57)") (pin "16") (pinfunction "16_16") (pintype "passive"))
    )
    (net (code "62") (name "/SERIAL4_TX") (class "Default")
      (node (ref "CON6_6") (pin "2") (pinfunction "2_2") (pintype "passive"))
      (node (ref "DF17(1.0H)-80DP-0.5V(57)") (pin "18") (pinfunction "18_18") (pintype "passive"))
    )
    (net (code "63") (name "/SERIAL5_RX") (class "Default")
      (node (ref "CON3_3") (pin "2") (pinfunction "2_2") (pintype "passive"))
      (node (ref "CON6_2") (pin "3") (pinfunction "3_3") (pintype "passive"))
      (node (ref "DF17(1.0H)-80DP-0.5V(57)") (pin "12") (pinfunction "12_12") (pintype "passive"))
    )
    (net (code "64") (name "/SERIAL5_TX") (class "Default")
      (node (ref "CON3_3") (pin "1") (pinfunction "1_1") (pintype "passive"))
      (node (ref "CON6_2") (pin "2") (pinfunction "2_2") (pintype "passive"))
      (node (ref "DF17(1.0H)-80DP-0.5V(57)") (pin "14") (pinfunction "14_14") (pintype "passive"))
    )
    (net (code "65") (name "/SPI_EXT_MISO") (class "Default")
      (node (ref "DF17(1.0H)-80DP-0.5V(57)") (pin "67") (pinfunction "67_67") (pintype "passive"))
    )
    (net (code "66") (name "/SPI_EXT_MOSI") (class "Default")
      (node (ref "DF17(1.0H)-80DP-0.5V(57)") (pin "51") (pinfunction "51_51") (pintype "passive"))
    )
    (net (code "67") (name "/SPI_EXT_SCK") (class "Default")
      (node (ref "DF17(1.0H)-80DP-0.5V(57)") (pin "73") (pinfunction "73_73") (pintype "passive"))
    )
    (net (code "68") (name "/VBUS") (class "Default")
      (node (ref "DF17(1.0H)-80DP-0.5V(57)") (pin "29") (pinfunction "29_29") (pintype "passive"))
      (node (ref "PSM") (pin "11") (pinfunction "VBUS_11") (pintype "passive"))
      (node (ref "PSM") (pin "20") (pinfunction "VDD_VBUS_20") (pintype "passive"))
      (node (ref "PSM") (pin "21") (pinfunction "VDD_VBUS_21") (pintype "passive"))
    )
    (net (code "69") (name "/VBUS_VALID") (class "Default")
      (node (ref "DF17(1.0H)-80DP-0.5V(57)") (pin "59") (pinfunction "59_59") (pintype "passive"))
      (node (ref "PSM") (pin "18") (pinfunction "!VBUS_VALID_18") (pintype "passive"))
    )
    (net (code "70") (name "/VDD_3V3_SPEKTRUM") (class "Default")
      (node (ref "PSM") (pin "1") (pinfunction "SPEK_1") (pintype "passive"))
    )
    (net (code "71") (name "/VDD_3V3_SPEKTRUM_EN") (class "Default")
      (node (ref "DF17(1.0H)-80DP-0.5V(57)") (pin "19") (pinfunction "19_19") (pintype "passive"))
      (node (ref "PSM") (pin "9") (pinfunction "VDD_3V3_SPEKTRUM_EN_9") (pintype "passive"))
    )
    (net (code "72") (name "/VDD_5V_BACKUP") (class "Default")
      (node (ref "PSM") (pin "22") (pinfunction "VDD_5V_BACKUP_22") (pintype "passive"))
      (node (ref "PSM") (pin "23") (pinfunction "VDD_5V_BACKUP_23") (pintype "passive"))
      (node (ref "U14") (pin "1") (pinfunction "1_1") (pintype "passive"))
      (node (ref "U14") (pin "2") (pinfunction "2_2") (pintype "passive"))
    )
    (net (code "73") (name "/VDD_5V_BRICK") (class "Default")
      (node (ref "PSM") (pin "24") (pinfunction "VDD_BRICK_IN_24") (pintype "passive"))
      (node (ref "PSM") (pin "25") (pinfunction "VDD_BRICK_IN_25") (pintype "passive"))
      (node (ref "U9") (pin "1") (pinfunction "1_1") (pintype "passive"))
      (node (ref "U9") (pin "2") (pinfunction "2_2") (pintype "passive"))
    )
    (net (code "74") (name "/VDD_5V_HIPOWER") (class "Default")
      (node (ref "PSM") (pin "5") (pinfunction "5V_HIPOWER_5") (pintype "passive"))
      (node (ref "U5") (pin "1") (pinfunction "1_1") (pintype "passive"))
    )
    (net (code "75") (name "/VDD_5V_HIPOWER_OC") (class "Default")
      (node (ref "DF17(1.0H)-80DP-0.5V(57)") (pin "45") (pinfunction "45_45") (pintype "passive"))
      (node (ref "PSM") (pin "7") (pinfunction "!VDD_5V_HIPOWER_OC_7") (pintype "passive"))
    )
    (net (code "76") (name "/VDD_5V_IN_PROT") (class "Default")
      (node (ref "DF17(1.0H)-80DP-0.5V(57)") (pin "61") (pinfunction "61_61") (pintype "passive"))
      (node (ref "DF17(1.0H)-80DP-0.5V(57)") (pin "63") (pinfunction "63_63") (pintype "passive"))
      (node (ref "PSM") (pin "15") (pinfunction "VDD_5V_IN_PROT_15") (pintype "passive"))
    )
    (net (code "77") (name "/VDD_5V_PERIPH") (class "Default")
      (node (ref "CON6_1") (pin "1") (pinfunction "1_1") (pintype "passive"))
      (node (ref "CON6_2") (pin "1") (pinfunction "1_1") (pintype "passive"))
      (node (ref "PSM") (pin "4") (pinfunction "5V_PERIPH_4") (pintype "passive"))
      (node (ref "U1") (pin "1") (pinfunction "1_1") (pintype "passive"))
      (node (ref "U11") (pin "1") (pinfunction "1_1") (pintype "passive"))
      (node (ref "U2") (pin "1") (pinfunction "1_1") (pintype "passive"))
      (node (ref "U3") (pin "1") (pinfunction "1_1") (pintype "passive"))
      (node (ref "U4") (pin "1") (pinfunction "1_1") (pintype "passive"))
      (node (ref "U6") (pin "1") (pinfunction "1_1") (pintype "passive"))
      (node (ref "U7") (pin "1") (pinfunction "1_1") (pintype "passive"))
      (node (ref "U8") (pin "1") (pinfunction "1_1") (pintype "passive"))
    )
    (net (code "78") (name "/VDD_5V_PERIPH_EN") (class "Default")
      (node (ref "DF17(1.0H)-80DP-0.5V(57)") (pin "27") (pinfunction "27_27") (pintype "passive"))
      (node (ref "PSM") (pin "10") (pinfunction "!VDD_5V_PERIPH_EN_10") (pintype "passive"))
    )
    (net (code "79") (name "/VDD_5V_PERIPH_OC") (class "Default")
      (node (ref "DF17(1.0H)-80DP-0.5V(57)") (pin "43") (pinfunction "43_43") (pintype "passive"))
      (node (ref "PSM") (pin "8") (pinfunction "!VDD_5V_PERIPH_OC_8") (pintype "passive"))
    )
    (net (code "80") (name "/VDD_BACKUP_VALID") (class "Default")
      (node (ref "DF17(1.0H)-80DP-0.5V(57)") (pin "57") (pinfunction "57_57") (pintype "passive"))
      (node (ref "PSM") (pin "17") (pinfunction "!VDD_BACKUP_VALID_17") (pintype "passive"))
    )
    (net (code "81") (name "/VDD_BRICK_VALID") (class "Default")
      (node (ref "DF17(1.0H)-80DP-0.5V(57)") (pin "55") (pinfunction "55_55") (pintype "passive"))
      (node (ref "PSM") (pin "16") (pinfunction "!VDD_BRICK_VALID_16") (pintype "passive"))
    )
    (net (code "82") (name "/VDD_SERVO") (class "Default")
      (node (ref "CON3_10") (pin "2") (pinfunction "2_2") (pintype "passive"))
      (node (ref "CON3_11") (pin "2") (pinfunction "2_2") (pintype "passive"))
      (node (ref "CON3_12") (pin "2") (pinfunction "2_2") (pintype "passive"))
      (node (ref "CON3_13") (pin "2") (pinfunction "2_2") (pintype "passive"))
      (node (ref "CON3_14") (pin "2") (pinfunction "2_2") (pintype "passive"))
      (node (ref "CON3_15") (pin "2") (pinfunction "2_2") (pintype "passive"))
      (node (ref "CON3_16") (pin "2") (pinfunction "2_2") (pintype "passive"))
      (node (ref "CON3_17") (pin "2") (pinfunction "2_2") (pintype "passive"))
      (node (ref "CON3_18") (pin "2") (pinfunction "2_2") (pintype "passive"))
      (node (ref "CON3_19") (pin "2") (pinfunction "2_2") (pintype "passive"))
      (node (ref "CON3_5") (pin "2") (pinfunction "2_2") (pintype "passive"))
      (node (ref "CON3_6") (pin "2") (pinfunction "2_2") (pintype "passive"))
      (node (ref "CON3_7") (pin "2") (pinfunction "2_2") (pintype "passive"))
      (node (ref "CON3_8") (pin "2") (pinfunction "2_2") (pintype "passive"))
      (node (ref "CON3_9") (pin "2") (pinfunction "2_2") (pintype "passive"))
      (node (ref "D12") (pin "2") (pinfunction "2_2") (pintype "passive"))
      (node (ref "DF17(1.0H)-80DP-0.5V(57)") (pin "53") (pinfunction "53_53") (pintype "passive"))
    )
    (net (code "83") (name "/VDD_SERVO_IN") (class "Default")
      (node (ref "DF17(1.0H)-80DP-0.5V(57)") (pin "9") (pinfunction "9_9") (pintype "passive"))
      (node (ref "PSM") (pin "19") (pinfunction "SERVO_IN_19") (pintype "passive"))
      (node (ref "U13") (pin "2") (pinfunction "2_2") (pintype "passive"))
    )
    (net (code "84") (name "GND") (class "Default")
      (node (ref "CON3_10") (pin "3") (pinfunction "3_3") (pintype "passive"))
      (node (ref "CON3_11") (pin "3") (pinfunction "3_3") (pintype "passive"))
      (node (ref "CON3_12") (pin "3") (pinfunction "3_3") (pintype "passive"))
      (node (ref "CON3_13") (pin "3") (pinfunction "3_3") (pintype "passive"))
      (node (ref "CON3_14") (pin "3") (pinfunction "3_3") (pintype "passive"))
      (node (ref "CON3_15") (pin "3") (pinfunction "3_3") (pintype "passive"))
      (node (ref "CON3_16") (pin "3") (pinfunction "3_3") (pintype "passive"))
      (node (ref "CON3_17") (pin "3") (pinfunction "3_3") (pintype "passive"))
      (node (ref "CON3_18") (pin "3") (pinfunction "3_3") (pintype "passive"))
      (node (ref "CON3_19") (pin "3") (pinfunction "3_3") (pintype "passive"))
      (node (ref "CON3_2") (pin "3") (pinfunction "3_3") (pintype "passive"))
      (node (ref "CON3_2") (pin "GND") (pinfunction "GND_GND") (pintype "passive"))
      (node (ref "CON3_3") (pin "3") (pinfunction "3_3") (pintype "passive"))
      (node (ref "CON3_4") (pin "3") (pinfunction "3_3") (pintype "passive"))
      (node (ref "CON3_5") (pin "3") (pinfunction "3_3") (pintype "passive"))
      (node (ref "CON3_6") (pin "3") (pinfunction "3_3") (pintype "passive"))
      (node (ref "CON3_7") (pin "3") (pinfunction "3_3") (pintype "passive"))
      (node (ref "CON3_8") (pin "3") (pinfunction "3_3") (pintype "passive"))
      (node (ref "CON3_9") (pin "3") (pinfunction "3_3") (pintype "passive"))
      (node (ref "CON4_1") (pin "4") (pinfunction "4_4") (pintype "passive"))
      (node (ref "CON4_1") (pin "GND") (pinfunction "GND_GND") (pintype "passive"))
      (node (ref "CON4_2") (pin "4") (pinfunction "4_4") (pintype "passive"))
      (node (ref "CON4_2") (pin "GND") (pinfunction "GND_GND") (pintype "passive"))
      (node (ref "CON4_3") (pin "4") (pinfunction "4_4") (pintype "passive"))
      (node (ref "CON4_3") (pin "GND") (pinfunction "GND_GND") (pintype "passive"))
      (node (ref "CON4_4") (pin "4") (pinfunction "4_4") (pintype "passive"))
      (node (ref "CON4_4") (pin "GND") (pinfunction "GND_GND") (pintype "passive"))
      (node (ref "CON4_5") (pin "4") (pinfunction "4_4") (pintype "passive"))
      (node (ref "CON4_5") (pin "GND") (pinfunction "GND_GND") (pintype "passive"))
      (node (ref "CON4_6") (pin "4") (pinfunction "4_4") (pintype "passive"))
      (node (ref "CON4_6") (pin "GND") (pinfunction "GND_GND") (pintype "passive"))
      (node (ref "CON6_1") (pin "6") (pinfunction "6_6") (pintype "passive"))
      (node (ref "CON6_1") (pin "GND") (pinfunction "GND_GND") (pintype "passive"))
      (node (ref "CON6_2") (pin "6") (pinfunction "6_6") (pintype "passive"))
      (node (ref "CON6_2") (pin "GND") (pinfunction "GND_GND") (pintype "passive"))
      (node (ref "CON6_3") (pin "6") (pinfunction "6_6") (pintype "passive"))
      (node (ref "CON6_3") (pin "GND") (pinfunction "GND_GND") (pintype "passive"))
      (node (ref "CON6_4") (pin "6") (pinfunction "6_6") (pintype "passive"))
      (node (ref "CON6_4") (pin "GND") (pinfunction "GND_GND") (pintype "passive"))
      (node (ref "CON6_5") (pin "8") (pinfunction "8_8") (pintype "passive"))
      (node (ref "CON6_5") (pin "GND") (pinfunction "GND_GND") (pintype "passive"))
      (node (ref "CON6_6") (pin "6") (pinfunction "6_6") (pintype "passive"))
      (node (ref "CON6_6") (pin "GND") (pinfunction "GND_GND") (pintype "passive"))
      (node (ref "D10") (pin "2") (pinfunction "2_2") (pintype "passive"))
      (node (ref "D11") (pin "2") (pinfunction "2_2") (pintype "passive"))
      (node (ref "D2") (pin "2") (pinfunction "2_2") (pintype "passive"))
      (node (ref "D3") (pin "2") (pinfunction "2_2") (pintype "passive"))
      (node (ref "D4") (pin "2") (pinfunction "2_2") (pintype "passive"))
      (node (ref "D5") (pin "2") (pinfunction "2_2") (pintype "passive"))
      (node (ref "D6") (pin "2") (pinfunction "2_2") (pintype "passive"))
      (node (ref "D7") (pin "2") (pinfunction "2_2") (pintype "passive"))
      (node (ref "D8") (pin "2") (pinfunction "2_2") (pintype "passive"))
      (node (ref "D9") (pin "2") (pinfunction "2_2") (pintype "passive"))
      (node (ref "DF17(1.0H)-80DP-0.5V(57)") (pin "13") (pinfunction "13_13") (pintype "passive"))
      (node (ref "DF17(1.0H)-80DP-0.5V(57)") (pin "15") (pinfunction "15_15") (pintype "passive"))
      (node (ref "DF17(1.0H)-80DP-0.5V(57)") (pin "HOLE1") (pinfunction "GND_HOLE1") (pintype "passive"))
      (node (ref "DF17(1.0H)-80DP-0.5V(57)") (pin "HOLE2") (pinfunction "GND_HOLE2") (pintype "passive"))
      (node (ref "DF17(1.0H)-80DP-0.5V(57)") (pin "SIT1") (pinfunction "GND_SIT1") (pintype "passive"))
      (node (ref "DF17(1.0H)-80DP-0.5V(57)") (pin "SIT2") (pinfunction "GND_SIT2") (pintype "passive"))
      (node (ref "LED1") (pin "2") (pinfunction "C_2") (pintype "passive"))
      (node (ref "PSM") (pin "14") (pinfunction "GND_14") (pintype "passive"))
      (node (ref "PSM") (pin "6") (pinfunction "GND_6") (pintype "passive"))
      (node (ref "U1") (pin "GND") (pinfunction "GND_GND") (pintype "passive"))
      (node (ref "U11") (pin "GND") (pinfunction "GND_GND") (pintype "passive"))
      (node (ref "U13") (pin "GND") (pinfunction "GND_GND") (pintype "passive"))
      (node (ref "U14") (pin "5") (pinfunction "5_5") (pintype "passive"))
      (node (ref "U14") (pin "6") (pinfunction "6_6") (pintype "passive"))
      (node (ref "U2") (pin "GND") (pinfunction "GND_GND") (pintype "passive"))
      (node (ref "U3") (pin "GND") (pinfunction "GND_GND") (pintype "passive"))
      (node (ref "U4") (pin "GND") (pinfunction "GND_GND") (pintype "passive"))
      (node (ref "U5") (pin "GND") (pinfunction "GND_GND") (pintype "passive"))
      (node (ref "U6") (pin "GND") (pinfunction "GND_GND") (pintype "passive"))
      (node (ref "U7") (pin "GND") (pinfunction "GND_GND") (pintype "passive"))
      (node (ref "U8") (pin "GND") (pinfunction "GND_GND") (pintype "passive"))
      (node (ref "U9") (pin "5") (pinfunction "5_5") (pintype "passive"))
      (node (ref "U9") (pin "6") (pinfunction "6_6") (pintype "passive"))
    )
    (net (code "85") (name "Net-(CON3_2-Pad1)") (class "Default")
      (node (ref "CON3_2") (pin "1") (pinfunction "1_1") (pintype "passive"))
      (node (ref "D2") (pin "1") (pinfunction "1_1") (pintype "passive"))
      (node (ref "U1") (pin "2") (pinfunction "2_2") (pintype "passive"))
    )
    (net (code "86") (name "Net-(CON4_2-Pad1)") (class "Default")
      (node (ref "CON4_2") (pin "1") (pinfunction "1_1") (pintype "passive"))
      (node (ref "D4") (pin "1") (pinfunction "1_1") (pintype "passive"))
      (node (ref "U3") (pin "2") (pinfunction "2_2") (pintype "passive"))
    )
    (net (code "87") (name "Net-(CON4_3-Pad1)") (class "Default")
      (node (ref "CON4_3") (pin "1") (pinfunction "1_1") (pintype "passive"))
      (node (ref "D5") (pin "1") (pinfunction "1_1") (pintype "passive"))
      (node (ref "U4") (pin "2") (pinfunction "2_2") (pintype "passive"))
    )
    (net (code "88") (name "Net-(CON4_4-Pad1)") (class "Default")
      (node (ref "CON4_4") (pin "1") (pinfunction "1_1") (pintype "passive"))
      (node (ref "D10") (pin "1") (pinfunction "1_1") (pintype "passive"))
      (node (ref "U11") (pin "2") (pinfunction "2_2") (pintype "passive"))
    )
    (net (code "89") (name "Net-(CON6_3-Pad1)") (class "Default")
      (node (ref "CON6_3") (pin "1") (pinfunction "1_1") (pintype "passive"))
      (node (ref "D6") (pin "1") (pinfunction "1_1") (pintype "passive"))
      (node (ref "U5") (pin "2") (pinfunction "2_2") (pintype "passive"))
    )
    (net (code "90") (name "Net-(CON6_4-Pad1)") (class "Default")
      (node (ref "CON6_4") (pin "1") (pinfunction "1_1") (pintype "passive"))
      (node (ref "D7") (pin "1") (pinfunction "1_1") (pintype "passive"))
      (node (ref "U6") (pin "2") (pinfunction "2_2") (pintype "passive"))
    )
    (net (code "91") (name "Net-(CON6_5-Pad1)") (class "Default")
      (node (ref "CON6_5") (pin "1") (pinfunction "1_1") (pintype "passive"))
      (node (ref "D8") (pin "1") (pinfunction "1_1") (pintype "passive"))
      (node (ref "U7") (pin "2") (pinfunction "2_2") (pintype "passive"))
    )
    (net (code "92") (name "Net-(CON6_6-Pad1)") (class "Default")
      (node (ref "CON6_6") (pin "1") (pinfunction "1_1") (pintype "passive"))
      (node (ref "D9") (pin "1") (pinfunction "1_1") (pintype "passive"))
      (node (ref "U8") (pin "2") (pinfunction "2_2") (pintype "passive"))
    )
    (net (code "93") (name "Net-(D11-Pad1)") (class "Default")
      (node (ref "D11") (pin "1") (pinfunction "1_1") (pintype "passive"))
      (node (ref "D12") (pin "1") (pinfunction "1_1") (pintype "passive"))
      (node (ref "U13") (pin "1") (pinfunction "1_1") (pintype "passive"))
    )
    (net (code "94") (name "unconnected-(DF17(1.0H)-80DP-0.5V(57)-Pad26)") (class "Default")
      (node (ref "DF17(1.0H)-80DP-0.5V(57)") (pin "26") (pinfunction "26_26") (pintype "passive"))
    )
    (net (code "95") (name "unconnected-(DF17(1.0H)-80DP-0.5V(57)-Pad65)") (class "Default")
      (node (ref "DF17(1.0H)-80DP-0.5V(57)") (pin "65") (pinfunction "65_65") (pintype "passive"))
    )
    (net (code "96") (name "unconnected-(PSM-NC-Pad2)") (class "Default")
      (node (ref "PSM") (pin "2") (pinfunction "NC_2") (pintype "passive"))
    )
    (net (code "97") (name "unconnected-(U9-Pad7)") (class "Default")
      (node (ref "U9") (pin "7") (pinfunction "7_7") (pintype "passive"))
    )
    (net (code "98") (name "unconnected-(U14-Pad7)") (class "Default")
      (node (ref "U14") (pin "7") (pinfunction "7_7") (pintype "passive"))
    )
  )
)
